# LEDs.net
KiCad netlist of a schematic drawn in Altium Designer
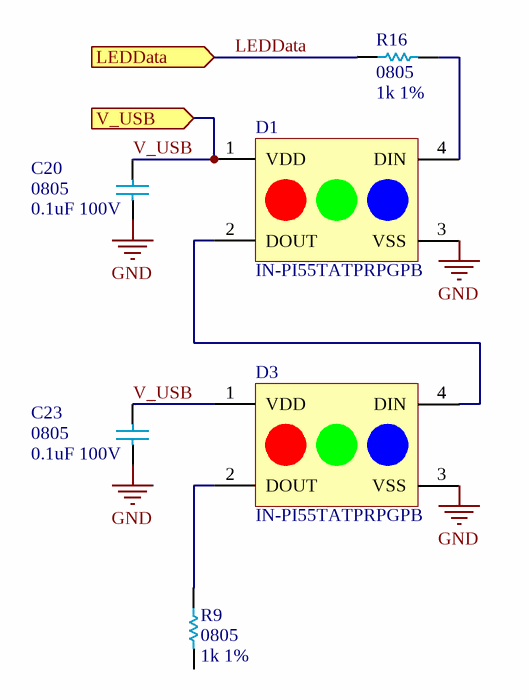
[diagram p0: LEDs.SchDoc]

(export (version "E")
  (design (tool "Eeschema 10.0.6"))
  (components
    (comp (ref "C20")
      (value "0805")
      (footprint "0805")
      (description "0805, X5R or better")
      (fields (field (name "ALTIUM_VALUE") "0.1uF 100V"))
      (libsource (lib "Chip_Passives") (part "Cap 0.1uF 100V"))
    )
    (comp (ref "C23")
      (value "0805")
      (footprint "0805")
      (description "0805, X5R or better")
      (fields (field (name "ALTIUM_VALUE") "0.1uF 100V"))
      (libsource (lib "Chip_Passives") (part "Cap 0.1uF 100V"))
    )
    (comp (ref "D1")
      (value "IN-PI55TATPRPGPB")
      (footprint "IN-PI55TATPRPGPB")
      (description "ADDRESS LED DISCRETE SERIAL RGB")
      (libsource (lib "LEDs") (part "IN-PI55TATPRPGPB"))
    )
    (comp (ref "D3")
      (value "IN-PI55TATPRPGPB")
      (footprint "IN-PI55TATPRPGPB")
      (description "ADDRESS LED DISCRETE SERIAL RGB")
      (libsource (lib "LEDs") (part "IN-PI55TATPRPGPB"))
    )
    (comp (ref "R9")
      (value "0805")
      (footprint "0805")
      (description "Chip resistor, 1/8W 100PPM")
      (fields (field (name "ALTIUM_VALUE") "1k 1%"))
      (libsource (lib "Chip_Passives") (part "Res 1k 1% 0805"))
    )
    (comp (ref "R16")
      (value "0805")
      (footprint "0805")
      (description "Chip resistor, 1/8W 100PPM")
      (fields (field (name "ALTIUM_VALUE") "1k 1%"))
      (libsource (lib "Chip_Passives") (part "Res 1k 1% 0805"))
    )
  )
  (nets
    (net (code "1") (name "/LEDData") (class "Default")
      (node (ref "R16") (pin "2") (pinfunction "2_2") (pintype "passive"))
    )
    (net (code "2") (name "/V_USB") (class "Default")
      (node (ref "C20") (pin "2") (pinfunction "2_2") (pintype "passive"))
      (node (ref "C23") (pin "2") (pinfunction "2_2") (pintype "passive"))
      (node (ref "D1") (pin "1") (pinfunction "VDD_1") (pintype "passive"))
      (node (ref "D3") (pin "1") (pinfunction "VDD_1") (pintype "passive"))
    )
    (net (code "3") (name "GND") (class "Default")
      (node (ref "C20") (pin "1") (pinfunction "1_1") (pintype "passive"))
      (node (ref "C23") (pin "1") (pinfunction "1_1") (pintype "passive"))
      (node (ref "D1") (pin "3") (pinfunction "VSS_3") (pintype "passive"))
      (node (ref "D3") (pin "3") (pinfunction "VSS_3") (pintype "passive"))
    )
    (net (code "4") (name "Net-(D1-DIN)") (class "Default")
      (node (ref "D1") (pin "4") (pinfunction "DIN_4") (pintype "passive"))
      (node (ref "R16") (pin "1") (pinfunction "1_1") (pintype "passive"))
    )
    (net (code "5") (name "Net-(D1-DOUT)") (class "Default")
      (node (ref "D1") (pin "2") (pinfunction "DOUT_2") (pintype "passive"))
      (node (ref "D3") (pin "4") (pinfunction "DIN_4") (pintype "passive"))
    )
    (net (code "6") (name "Net-(D3-DOUT)") (class "Default")
      (node (ref "D3") (pin "2") (pinfunction "DOUT_2") (pintype "passive"))
      (node (ref "R9") (pin "2") (pinfunction "2_2") (pintype "passive"))
    )
    (net (code "7") (name "unconnected-(R9-Pad1)") (class "Default")
      (node (ref "R9") (pin "1") (pinfunction "1_1") (pintype "passive"))
    )
  )
)
